# AQM_with_ESP32.net
KiCad netlist of a schematic drawn in Altium Designer
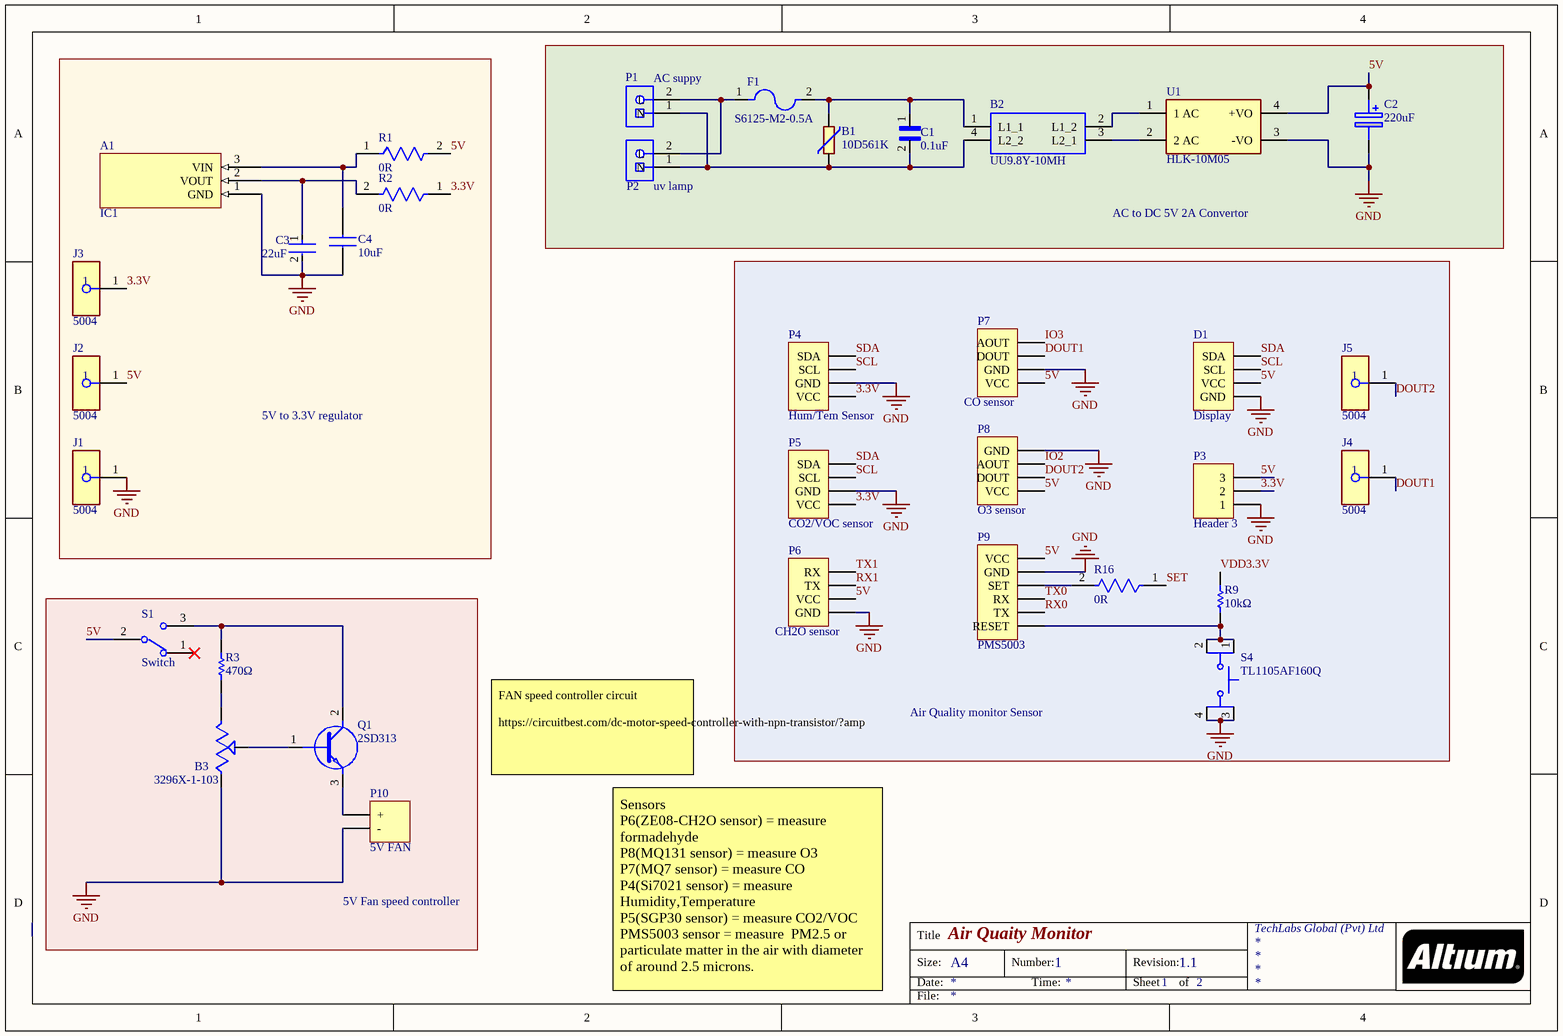
[diagram p0: AQM with ESP32.SchDoc]

(export (version "E")
  (design (tool "Eeschema 10.0.6"))
  (components
    (comp (ref "A1")
      (value "IC1")
      (footprint "SOT89-150P350X150-3N")
      (fields
        (field (name "MANUFACTURER") "YONGYUTAI")
        (field (name "MFR. PART #") "AMS1117-3.3")
        (field (name "LCSC PART #") "C2904742")
      )
      (libsource (lib "AMS1117-3.3") (part "IC?"))
    )
    (comp (ref "B1")
      (value "10D561K")
      (footprint "10D561K")
      (description "920V 42.3J 180pF@1kHz 460V 350V 504V~616V 2.5kA Plugin Varistors ROHS")
      (fields (field (name "LCSC PART #") "C113236") (field (name "MANUFACTURER") "Hongzhi Elec"))
      (libsource (lib "10D561K") (part "10D561K"))
    )
    (comp (ref "B2")
      (value "UU9.8Y-10MH")
      (footprint "UU98Y10MH")
      (description "10mH@1kHz 1.2Ω 2 500mA 50V Plugin Common Mode Filters ROHS")
      (fields
        (field (name "MANUFACTURER") "FH (Guangdong Fenghua Advanced Tech)")
        (field (name "LCSC PART #") "C75192")
      )
      (libsource (lib "UU9.8Y-10MH") (part "UU9.8Y-10MH"))
    )
    (comp (ref "B3")
      (value "3296X-1-103")
      (footprint "3296X1223LF")
      (description "±10% 10kΩ Plugin Variable Resistors/Potentiometers ROHS")
      (fields
        (field (name "LCSC PART #") "C118955")
        (field (name "MANUFACTURER") "BOCHEN(Chengdu Guosheng Tech)")
      )
      (libsource (lib "3296X-1-103") (part "3296X-1-103"))
    )
    (comp (ref "C1")
      (value "0.1uF")
      (footprint "MPX-104K275VAC-C-D2")
      (description "X2 100nF ±10% 275V Plugin,P=15mm Suppression Capacitors ROHS")
      (fields (field (name "LCSC PART #") "C914484") (field (name "MANUFACTURER") "NDF"))
      (libsource (lib "X2-104K-275VAC") (part "MPX-104K275VAC-C-D2"))
    )
    (comp (ref "C2")
      (value "220uF")
      (footprint "CAPAE830X1050N")
      (fields
        (field (name "MANUFACTURER") "Nichicon")
        (field (name "MFR. PART #") "UUR1C221MNL1GS")
        (field (name "LCSC PART #") "C445237")
      )
      (libsource (lib "UUR1C221MNL1GS") (part "UUR1C221MNL1GS"))
    )
    (comp (ref "C3")
      (value "22uF")
      (footprint "FP-GRM219-0_2-0_15-IPC_A")
      (description "Chip Multilayer Ceramic Capacitors for General Purpose, 0805, 22uF, X5R, 15%, 20%, 16V")
      (fields (field (name "MFR. PART #") "GRM219R61C226ME15L") (field (name "LCSC PART #") "C162295"))
      (libsource (lib "Altium Content Vault") (part "b4654b650e69147ec39a6b967a45e02"))
    )
    (comp (ref "C4")
      (value "10uF")
      (footprint "CL05A106MQ5NUNC")
      (description "6.3V 10uF X5R ±20% 0402 Multilayer Ceramic Capacitors MLCC - SMD/SMT ROHS")
      (fields
        (field (name "MANUFACTURER") "Samsung Electro-Mechanics")
        (field (name "MFR. PART #") "CL05A106MQ5NUNC")
      )
      (libsource (lib "CL05A106MQ5NUNC") (part "CL05A106MQ5NUNC"))
    )
    (comp (ref "D1")
      (value "Display")
      (footprint "HDR1X4")
      (description "Header, 4-Pin")
      (fields (field (name "PUBLISHER") "Altium Limited"))
      (libsource (lib "") (part "Header 4_1"))
    )
    (comp (ref "F1")
      (value "S6125-M2-0.5A")
      (footprint "CAPC6125X25N")
      (description "SMD Fuses ROHS")
      (fields (field (name "LCSC PART #") "C845172") (field (name "MANUFACTURER") "SART(Nanjing Sart Tech)"))
      (libsource (lib "S6125-M2-0.5A") (part "S6125-M2-0.5A"))
    )
    (comp (ref "J1")
      (value "5004")
      (footprint "FP-5004-MFG")
      (description "PC TEST POINT MINIATURE YELLOW")
      (fields (field (name "MANUFACTURER") "Keystone") (field (name "LCSC PART #") "C2906762"))
      (libsource (lib "Altium Content Vault") (part "98815daf2f2c152b0c43f5ab9800df6"))
    )
    (comp (ref "J2")
      (value "5004")
      (footprint "FP-5004-MFG")
      (description "PC TEST POINT MINIATURE YELLOW")
      (fields (field (name "MANUFACTURER") "Keystone") (field (name "LCSC PART #") "C2906762"))
      (libsource (lib "Altium Content Vault") (part "98815daf2f2c152b0c43f5ab9800df6"))
    )
    (comp (ref "J3")
      (value "5004")
      (footprint "FP-5004-MFG")
      (description "PC TEST POINT MINIATURE YELLOW")
      (fields (field (name "MANUFACTURER") "Keystone") (field (name "LCSC PART #") "C2906762"))
      (libsource (lib "Altium Content Vault") (part "98815daf2f2c152b0c43f5ab9800df6"))
    )
    (comp (ref "J4")
      (value "5004")
      (footprint "FP-5004-MFG")
      (description "PC TEST POINT MINIATURE YELLOW")
      (fields (field (name "MANUFACTURER") "Keystone") (field (name "LCSC PART #") "C2906762"))
      (libsource (lib "Altium Content Vault") (part "98815daf2f2c152b0c43f5ab9800df6"))
    )
    (comp (ref "J5")
      (value "5004")
      (footprint "FP-5004-MFG")
      (description "PC TEST POINT MINIATURE YELLOW")
      (fields (field (name "MANUFACTURER") "Keystone") (field (name "LCSC PART #") "C2906762"))
      (libsource (lib "Altium Content Vault") (part "98815daf2f2c152b0c43f5ab9800df6"))
    )
    (comp (ref "P1")
      (value "AC suppy")
      (footprint "PHOE-1729128-2_V")
      (description "13.5A 400V Green Straight pin 5.08mm 1 2 Plugin,P=5.08mm Screw terminal ROHS")
      (fields (field (name "MFR. PART #") "1729128") (field (name "LCSC PART #") "C91153"))
      (libsource (lib "Altium Content Vault") (part "CN-2P-F-R2"))
    )
    (comp (ref "P2")
      (value "uv lamp")
      (footprint "PHOE-1729128-2_V")
      (description "13.5A 400V Green Straight pin 5.08mm 1 2 Plugin,P=5.08mm Screw terminal ROHS")
      (fields (field (name "MFR. PART #") "1729128") (field (name "LCSC PART #") "C91153"))
      (libsource (lib "Altium Content Vault") (part "CN-2P-F-R2"))
    )
    (comp (ref "P3")
      (value "Header 3")
      (footprint "HDR1X3")
      (description "Header, 3-Pin")
      (fields (field (name "PUBLISHER") "Altium Limited"))
      (libsource (lib "Miscellaneous Connectors") (part "Header 3"))
    )
    (comp (ref "P4")
      (value "Hum/Tem Sensor")
      (footprint "HDR1X4")
      (description "Si7021 Header, 4-Pin")
      (libsource (lib "") (part "Header 4_2"))
    )
    (comp (ref "P5")
      (value "CO2/VOC sensor")
      (footprint "HDR1X4")
      (description "SGP30 Header, 4-Pin")
      (fields (field (name "PUBLISHER") "Altium Limited"))
      (libsource (lib "") (part "Header 4_2"))
    )
    (comp (ref "P6")
      (value "CH2O sensor")
      (footprint "HDR1X4")
      (description "- Sensor Modules ROHS")
      (fields
        (field (name "MFR. PART #") "ZE08-CH2O")
        (field (name "MANUFACTURER") "Zhengzhou Winsen Elec Tech")
      )
      (libsource (lib "") (part "Header 4_3"))
    )
    (comp (ref "P7")
      (value "CO sensor")
      (footprint "HDR1X4")
      (description "MQ7 Header, 4-Pin")
      (fields (field (name "PUBLISHER") "Altium Limited"))
      (libsource (lib "") (part "Header 4_4"))
    )
    (comp (ref "P8")
      (value "O3 sensor")
      (footprint "HDR1X4")
      (description "MQ131 Header, 4-Pin")
      (fields (field (name "PUBLISHER") "Altium Limited"))
      (libsource (lib "Miscellaneous Connectors") (part "Header 4"))
    )
    (comp (ref "P9")
      (value "PMS5003")
      (footprint "HDR1X6")
      (description "PMS5003 Sensor Modules ROHS")
      (fields (field (name "LCSC PART #") "C91431") (field (name "MANUFACTURER") "Beijing Plantower"))
      (libsource (lib "Miscellaneous Connectors") (part "Header 6"))
    )
    (comp (ref "P10")
      (value "5V FAN")
      (footprint "HDR1X2")
      (description "Header, 2-Pin")
      (fields (field (name "PUBLISHER") "Altium Limited"))
      (libsource (lib "Miscellaneous Connectors") (part "Header 2"))
    )
    (comp (ref "Q1")
      (value "2SD313")
      (footprint "TO304P498X1010X2089-3P")
      (description "NPN Transistor, TO-220")
      (fields
        (field (name "LCSC PART #") "C3031919")
        (field (name "MANUFACTURER") "Jiangsu Changjing Electronics Technology Co., Ltd.")
      )
      (libsource (lib "2SD313") (part "2SD313"))
    )
    (comp (ref "R1")
      (value "0R")
      (footprint "FP-RC0402-0_4-IPC_A")
      (description "RES SMD 0 OHM JUMPER 1/16W 0402")
      (fields (field (name "MANUFACTURER") "Yageo") (field (name "LCSC PART #") "C106231"))
      (libsource (lib "Altium Content Vault") (part "1029c3af85768c4190bb7ad29bc67b5"))
    )
    (comp (ref "R2")
      (value "0R")
      (footprint "FP-RC0402-0_4-IPC_A")
      (description "RES SMD 0 OHM JUMPER 1/16W 0402")
      (fields (field (name "MANUFACTURER") "Yageo") (field (name "LCSC PART #") "C106231"))
      (libsource (lib "Altium Content Vault") (part "1029c3af85768c4190bb7ad29bc67b5"))
    )
    (comp (ref "R3")
      (value "470Ω")
      (footprint "RESC1608X55X25LL10T15")
      (fields
        (field (name "LCSC PART #") "C114669")
        (field (name "MFR. PART #") "RC0603FR-07470RL")
        (field (name "MANUFACTURER") "YAGEO")
      )
      (libsource (lib "Altium Content Vault") (part "RES-2"))
    )
    (comp (ref "R9")
      (value "10kΩ")
      (footprint "RESC1005X40X25LL05T10")
      (fields
        (field (name "MFR. PART #") "RC0402FR-0710KL")
        (field (name "MANUFACTURER") "YAGEO")
        (field (name "LCSC PART #") "C60490")
      )
      (libsource (lib "Altium Content Vault") (part "RES"))
    )
    (comp (ref "R16")
      (value "0R")
      (footprint "FP-RC0402-0_4-IPC_A")
      (description "RES SMD 0 OHM JUMPER 1/16W 0402")
      (fields (field (name "MANUFACTURER") "Yageo") (field (name "LCSC PART #") "C106231"))
      (libsource (lib "Altium Content Vault") (part "1029c3af85768c4190bb7ad29bc67b5"))
    )
    (comp (ref "S1")
      (value "Switch")
      (footprint "SK3245SL1A")
      (fields
        (field (name "MANUFACTURER") "XKB Connectivity")
        (field (name "MFR. PART #") "SK-3245S-L1-A")
        (field (name "LCSC PART #") "C405951")
      )
      (libsource (lib "SK-3245S-L1-A") (part "SK-3245S-L1-A"))
    )
    (comp (ref "S4")
      (value "TL1105AF160Q")
      (footprint "TL1105AF160Q")
      (description "6mm 1.4mm Round Button 50mA Straight 6mm SPST 12V Plugin,6x6mm Tactile Switches ROHS")
      (fields (field (name "MANUFACTURER") "E-Switch") (field (name "LCSC PART #") "C273465"))
      (libsource (lib "TL1105AF160Q") (part "TL1105AF160Q"))
    )
    (comp (ref "U1")
      (value "HLK-10M05")
      (footprint "FP-HLK-10M05-MFG")
      (description "5V 2A 90VAC~265VAC 1 120V~350V Isolated Regulated 10W AC-DC 80% Plugin Power Modules ROHS")
      (fields (field (name "MANUFACTURER") "HI-LINK") (field (name "LCSC PART #") "C403745"))
      (libsource (lib "Altium Content Vault") (part "a65b17ccb3a75dffb3c3e849074403b"))
    )
  )
  (nets
    (net (code "1") (name "/3.3V") (class "Default")
      (node (ref "J3") (pin "1") (pinfunction "1_1") (pintype "passive"))
      (node (ref "P3") (pin "2") (pinfunction "2_2") (pintype "passive"))
      (node (ref "P4") (pin "1") (pinfunction "VCC_1") (pintype "passive"))
      (node (ref "P5") (pin "1") (pinfunction "VCC_1") (pintype "passive"))
      (node (ref "R2") (pin "1") (pinfunction "1_1") (pintype "passive"))
    )
    (net (code "2") (name "/5V") (class "Default")
      (node (ref "C2") (pin "1") (pinfunction "+_1") (pintype "passive"))
      (node (ref "D1") (pin "2") (pinfunction "VCC_2") (pintype "passive"))
      (node (ref "J2") (pin "1") (pinfunction "1_1") (pintype "passive"))
      (node (ref "P3") (pin "3") (pinfunction "3_3") (pintype "passive"))
      (node (ref "P6") (pin "2") (pinfunction "VCC_2") (pintype "passive"))
      (node (ref "P7") (pin "1") (pinfunction "VCC_1") (pintype "passive"))
      (node (ref "P8") (pin "1") (pinfunction "VCC_1") (pintype "passive"))
      (node (ref "P9") (pin "6") (pinfunction "VCC_6") (pintype "passive"))
      (node (ref "R1") (pin "2") (pinfunction "2_2") (pintype "passive"))
      (node (ref "S1") (pin "2") (pinfunction "2_2") (pintype "passive"))
      (node (ref "U1") (pin "4") (pinfunction "+VO_4") (pintype "power_in"))
    )
    (net (code "3") (name "/DOUT1") (class "Default")
      (node (ref "J4") (pin "1") (pinfunction "1_1") (pintype "passive"))
      (node (ref "P7") (pin "3") (pinfunction "DOUT_3") (pintype "passive"))
    )
    (net (code "4") (name "/DOUT2") (class "Default")
      (node (ref "J5") (pin "1") (pinfunction "1_1") (pintype "passive"))
      (node (ref "P8") (pin "2") (pinfunction "DOUT_2") (pintype "passive"))
    )
    (net (code "5") (name "/IO2") (class "Default")
      (node (ref "P8") (pin "3") (pinfunction "AOUT_3") (pintype "passive"))
    )
    (net (code "6") (name "/IO3") (class "Default")
      (node (ref "P7") (pin "4") (pinfunction "AOUT_4") (pintype "passive"))
    )
    (net (code "7") (name "/RX0") (class "Default")
      (node (ref "P9") (pin "2") (pinfunction "TX_2") (pintype "passive"))
    )
    (net (code "8") (name "/RX1") (class "Default")
      (node (ref "P6") (pin "3") (pinfunction "TX_3") (pintype "passive"))
    )
    (net (code "9") (name "/SCL") (class "Default")
      (node (ref "D1") (pin "3") (pinfunction "SCL_3") (pintype "passive"))
      (node (ref "P4") (pin "3") (pinfunction "SCL_3") (pintype "passive"))
      (node (ref "P5") (pin "3") (pinfunction "SCL_3") (pintype "passive"))
    )
    (net (code "10") (name "/SDA") (class "Default")
      (node (ref "D1") (pin "4") (pinfunction "SDA_4") (pintype "passive"))
      (node (ref "P4") (pin "4") (pinfunction "SDA_4") (pintype "passive"))
      (node (ref "P5") (pin "4") (pinfunction "SDA_4") (pintype "passive"))
    )
    (net (code "11") (name "/SET") (class "Default")
      (node (ref "R16") (pin "1") (pinfunction "1_1") (pintype "passive"))
    )
    (net (code "12") (name "/TX0") (class "Default")
      (node (ref "P9") (pin "3") (pinfunction "RX_3") (pintype "passive"))
    )
    (net (code "13") (name "/TX1") (class "Default")
      (node (ref "P6") (pin "4") (pinfunction "RX_4") (pintype "passive"))
    )
    (net (code "14") (name "/VDD3.3V") (class "Default")
      (node (ref "R9") (pin "1") (pinfunction "1_1") (pintype "passive"))
    )
    (net (code "15") (name "GND") (class "Default")
      (node (ref "A1") (pin "1") (pinfunction "GND_1") (pintype "input"))
      (node (ref "B3") (pin "1") (pinfunction "A_1") (pintype "passive"))
      (node (ref "C2") (pin "2") (pinfunction "-_2") (pintype "passive"))
      (node (ref "C3") (pin "2") (pinfunction "2_2") (pintype "passive"))
      (node (ref "C4") (pin "1") (pinfunction "1_1") (pintype "passive"))
      (node (ref "D1") (pin "1") (pinfunction "GND_1") (pintype "passive"))
      (node (ref "J1") (pin "1") (pinfunction "1_1") (pintype "passive"))
      (node (ref "P10") (pin "2") (pinfunction "-_2") (pintype "passive"))
      (node (ref "P3") (pin "1") (pinfunction "1_1") (pintype "passive"))
      (node (ref "P4") (pin "2") (pinfunction "GND_2") (pintype "passive"))
      (node (ref "P5") (pin "2") (pinfunction "GND_2") (pintype "passive"))
      (node (ref "P6") (pin "1") (pinfunction "GND_1") (pintype "passive"))
      (node (ref "P7") (pin "2") (pinfunction "GND_2") (pintype "passive"))
      (node (ref "P8") (pin "4") (pinfunction "GND_4") (pintype "passive"))
      (node (ref "P9") (pin "5") (pinfunction "GND_5") (pintype "passive"))
      (node (ref "S4") (pin "3") (pinfunction "3_3") (pintype "passive"))
      (node (ref "S4") (pin "4") (pinfunction "4_4") (pintype "passive"))
      (node (ref "U1") (pin "3") (pinfunction "-VO_3") (pintype "power_in"))
    )
    (net (code "16") (name "Net-(A1-VIN)") (class "Default")
      (node (ref "A1") (pin "3") (pinfunction "VIN_3") (pintype "input"))
      (node (ref "C4") (pin "2") (pinfunction "2_2") (pintype "passive"))
      (node (ref "R1") (pin "1") (pinfunction "1_1") (pintype "passive"))
    )
    (net (code "17") (name "Net-(A1-VOUT)") (class "Default")
      (node (ref "A1") (pin "2") (pinfunction "VOUT_2") (pintype "input"))
      (node (ref "C3") (pin "1") (pinfunction "1_1") (pintype "passive"))
      (node (ref "R2") (pin "2") (pinfunction "2_2") (pintype "passive"))
    )
    (net (code "18") (name "Net-(B2-L1_1)") (class "Default")
      (node (ref "B1") (pin "1") (pinfunction "1_1") (pintype "passive"))
      (node (ref "B2") (pin "1") (pinfunction "L1_1_1") (pintype "passive"))
      (node (ref "C1") (pin "1") (pinfunction "1_1") (pintype "passive"))
      (node (ref "F1") (pin "2") (pinfunction "2_2") (pintype "passive"))
    )
    (net (code "19") (name "Net-(B2-L1_2)") (class "Default")
      (node (ref "B2") (pin "2") (pinfunction "L1_2_2") (pintype "passive"))
      (node (ref "U1") (pin "1") (pinfunction "1_AC_1") (pintype "passive"))
    )
    (net (code "20") (name "Net-(B2-L2_1)") (class "Default")
      (node (ref "B2") (pin "3") (pinfunction "L2_1_3") (pintype "passive"))
      (node (ref "U1") (pin "2") (pinfunction "2_AC_2") (pintype "passive"))
    )
    (net (code "21") (name "Net-(B2-L2_2)") (class "Default")
      (node (ref "B1") (pin "2") (pinfunction "2_2") (pintype "passive"))
      (node (ref "B2") (pin "4") (pinfunction "L2_2_4") (pintype "passive"))
      (node (ref "C1") (pin "2") (pinfunction "2_2") (pintype "passive"))
      (node (ref "P1") (pin "1") (pinfunction "N_1") (pintype "passive"))
      (node (ref "P2") (pin "1") (pinfunction "N_1") (pintype "passive"))
    )
    (net (code "22") (name "Net-(B3-B)") (class "Default")
      (node (ref "B3") (pin "2") (pinfunction "B_2") (pintype "passive"))
      (node (ref "Q1") (pin "1") (pinfunction "B_1") (pintype "passive"))
    )
    (net (code "23") (name "Net-(B3-C)") (class "Default")
      (node (ref "B3") (pin "3") (pinfunction "C_3") (pintype "passive"))
      (node (ref "R3") (pin "1") (pinfunction "1_1") (pintype "passive"))
    )
    (net (code "24") (name "Net-(P1-L)") (class "Default")
      (node (ref "F1") (pin "1") (pinfunction "1_1") (pintype "passive"))
      (node (ref "P1") (pin "2") (pinfunction "L_2") (pintype "passive"))
      (node (ref "P2") (pin "2") (pinfunction "L_2") (pintype "passive"))
    )
    (net (code "25") (name "Net-(P9-RESET)") (class "Default")
      (node (ref "P9") (pin "1") (pinfunction "RESET_1") (pintype "passive"))
      (node (ref "R9") (pin "2") (pinfunction "2_2") (pintype "passive"))
      (node (ref "S4") (pin "1") (pinfunction "1_1") (pintype "passive"))
      (node (ref "S4") (pin "2") (pinfunction "2_2") (pintype "passive"))
    )
    (net (code "26") (name "Net-(P9-SET)") (class "Default")
      (node (ref "P9") (pin "4") (pinfunction "SET_4") (pintype "passive"))
      (node (ref "R16") (pin "2") (pinfunction "2_2") (pintype "passive"))
    )
    (net (code "27") (name "Net-(P10-+)") (class "Default")
      (node (ref "P10") (pin "1") (pinfunction "+_1") (pintype "passive"))
      (node (ref "Q1") (pin "3") (pinfunction "E_3") (pintype "passive"))
    )
    (net (code "28") (name "Net-(Q1-C)") (class "Default")
      (node (ref "Q1") (pin "2") (pinfunction "C_2") (pintype "passive"))
      (node (ref "R3") (pin "2") (pinfunction "2_2") (pintype "passive"))
      (node (ref "S1") (pin "3") (pinfunction "3_3") (pintype "passive"))
    )
    (net (code "29") (name "unconnected-(S1-Pad1)") (class "Default")
      (node (ref "S1") (pin "1") (pinfunction "1_1") (pintype "passive+no_connect"))
    )
  )
)
